# Schematic.net
KiCad netlist of a schematic drawn in Altium Designer
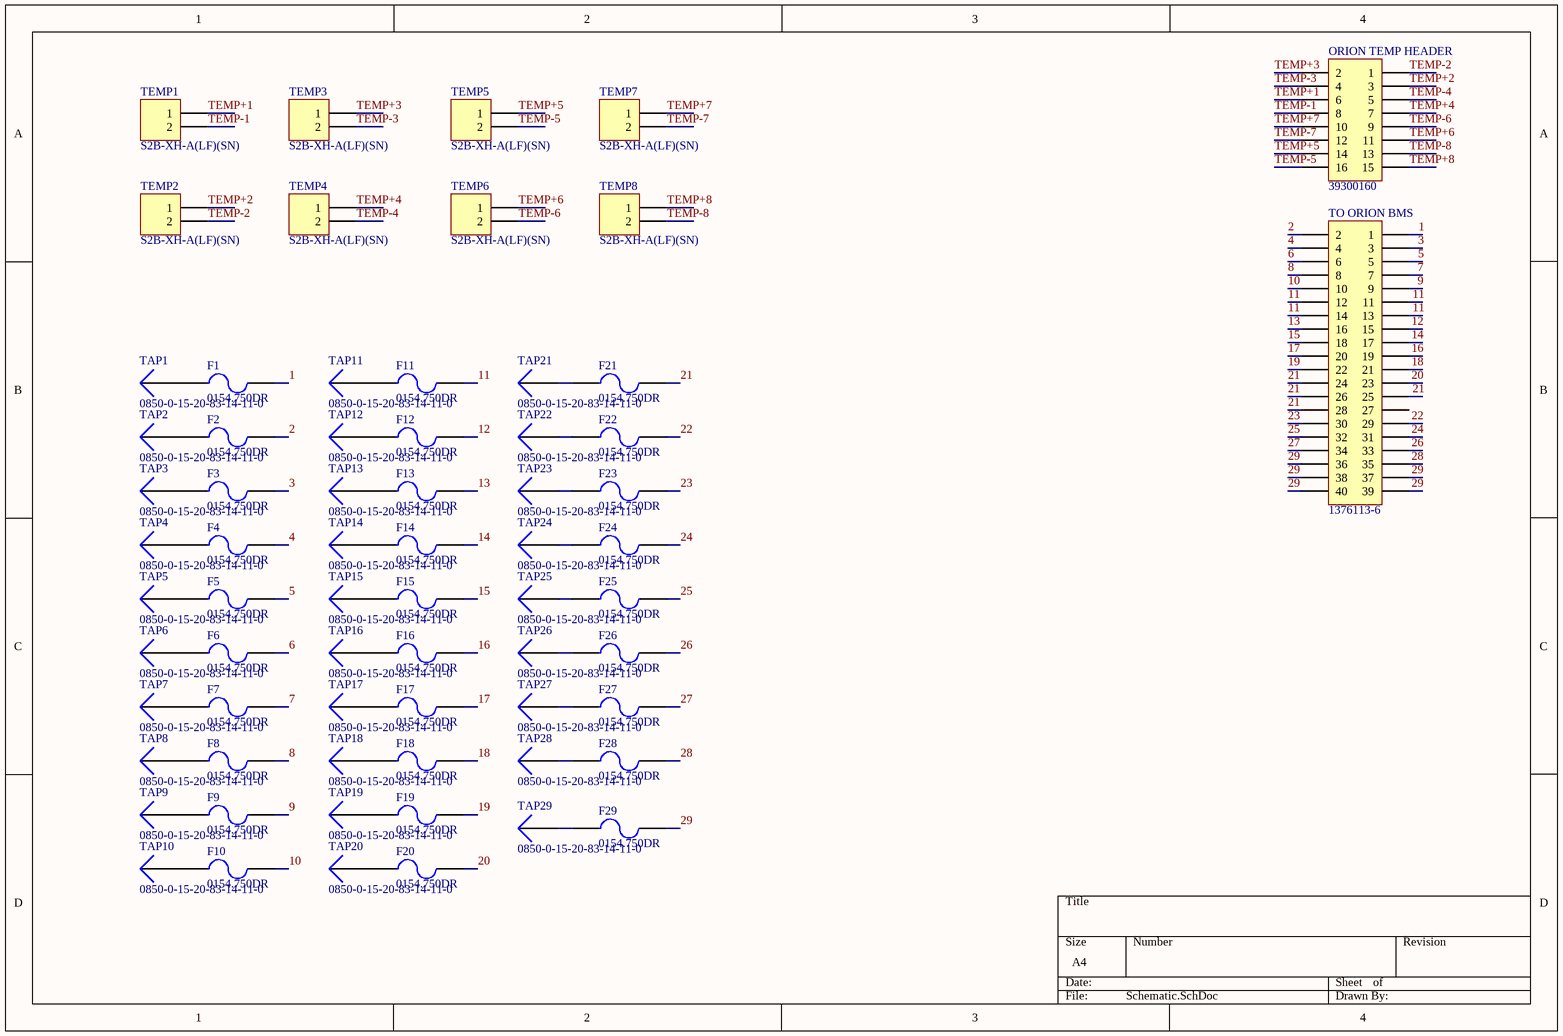
[diagram p0: Schematic.SchDoc]

(export (version "E")
  (design (tool "Eeschema 10.0.6"))
  (components
    (comp (ref "F1")
      (value "0154.750DR")
      (footprint "Omni BLOK 0154")
      (description "FUSE BOARD MNT 750MA 125VAC/VDC")
      (fields
        (field (name "MANUFACTURER") "LittelFuse Inc")
        (field (name "DIGIKEY PART NUMBER") "F1221CT-ND")
      )
      (libsource (lib "ts_20-standard-library") (part "Fuse"))
    )
    (comp (ref "F2")
      (value "0154.750DR")
      (footprint "Omni BLOK 0154")
      (description "FUSE BOARD MNT 750MA 125VAC/VDC")
      (fields
        (field (name "MANUFACTURER") "LittelFuse Inc")
        (field (name "DIGIKEY PART NUMBER") "F1221CT-ND")
      )
      (libsource (lib "ts_20-standard-library") (part "Fuse"))
    )
    (comp (ref "F3")
      (value "0154.750DR")
      (footprint "Omni BLOK 0154")
      (description "FUSE BOARD MNT 750MA 125VAC/VDC")
      (fields
        (field (name "MANUFACTURER") "LittelFuse Inc")
        (field (name "DIGIKEY PART NUMBER") "F1221CT-ND")
      )
      (libsource (lib "ts_20-standard-library") (part "Fuse"))
    )
    (comp (ref "F4")
      (value "0154.750DR")
      (footprint "Omni BLOK 0154")
      (description "FUSE BOARD MNT 750MA 125VAC/VDC")
      (fields
        (field (name "MANUFACTURER") "LittelFuse Inc")
        (field (name "DIGIKEY PART NUMBER") "F1221CT-ND")
      )
      (libsource (lib "ts_20-standard-library") (part "Fuse"))
    )
    (comp (ref "F5")
      (value "0154.750DR")
      (footprint "Omni BLOK 0154")
      (description "FUSE BOARD MNT 750MA 125VAC/VDC")
      (fields
        (field (name "MANUFACTURER") "LittelFuse Inc")
        (field (name "DIGIKEY PART NUMBER") "F1221CT-ND")
      )
      (libsource (lib "ts_20-standard-library") (part "Fuse"))
    )
    (comp (ref "F6")
      (value "0154.750DR")
      (footprint "Omni BLOK 0154")
      (description "FUSE BOARD MNT 750MA 125VAC/VDC")
      (fields
        (field (name "MANUFACTURER") "LittelFuse Inc")
        (field (name "DIGIKEY PART NUMBER") "F1221CT-ND")
      )
      (libsource (lib "ts_20-standard-library") (part "Fuse"))
    )
    (comp (ref "F7")
      (value "0154.750DR")
      (footprint "Omni BLOK 0154")
      (description "FUSE BOARD MNT 750MA 125VAC/VDC")
      (fields
        (field (name "MANUFACTURER") "LittelFuse Inc")
        (field (name "DIGIKEY PART NUMBER") "F1221CT-ND")
      )
      (libsource (lib "ts_20-standard-library") (part "Fuse"))
    )
    (comp (ref "F8")
      (value "0154.750DR")
      (footprint "Omni BLOK 0154")
      (description "FUSE BOARD MNT 750MA 125VAC/VDC")
      (fields
        (field (name "MANUFACTURER") "LittelFuse Inc")
        (field (name "DIGIKEY PART NUMBER") "F1221CT-ND")
      )
      (libsource (lib "ts_20-standard-library") (part "Fuse"))
    )
    (comp (ref "F9")
      (value "0154.750DR")
      (footprint "Omni BLOK 0154")
      (description "FUSE BOARD MNT 750MA 125VAC/VDC")
      (fields
        (field (name "MANUFACTURER") "LittelFuse Inc")
        (field (name "DIGIKEY PART NUMBER") "F1221CT-ND")
      )
      (libsource (lib "ts_20-standard-library") (part "Fuse"))
    )
    (comp (ref "F10")
      (value "0154.750DR")
      (footprint "Omni BLOK 0154")
      (description "FUSE BOARD MNT 750MA 125VAC/VDC")
      (fields
        (field (name "MANUFACTURER") "LittelFuse Inc")
        (field (name "DIGIKEY PART NUMBER") "F1221CT-ND")
      )
      (libsource (lib "ts_20-standard-library") (part "Fuse"))
    )
    (comp (ref "F11")
      (value "0154.750DR")
      (footprint "Omni BLOK 0154")
      (description "FUSE BOARD MNT 750MA 125VAC/VDC")
      (fields
        (field (name "MANUFACTURER") "LittelFuse Inc")
        (field (name "DIGIKEY PART NUMBER") "F1221CT-ND")
      )
      (libsource (lib "ts_20-standard-library") (part "Fuse"))
    )
    (comp (ref "F12")
      (value "0154.750DR")
      (footprint "Omni BLOK 0154")
      (description "FUSE BOARD MNT 750MA 125VAC/VDC")
      (fields
        (field (name "MANUFACTURER") "LittelFuse Inc")
        (field (name "DIGIKEY PART NUMBER") "F1221CT-ND")
      )
      (libsource (lib "ts_20-standard-library") (part "Fuse"))
    )
    (comp (ref "F13")
      (value "0154.750DR")
      (footprint "Omni BLOK 0154")
      (description "FUSE BOARD MNT 750MA 125VAC/VDC")
      (fields
        (field (name "MANUFACTURER") "LittelFuse Inc")
        (field (name "DIGIKEY PART NUMBER") "F1221CT-ND")
      )
      (libsource (lib "ts_20-standard-library") (part "Fuse"))
    )
    (comp (ref "F14")
      (value "0154.750DR")
      (footprint "Omni BLOK 0154")
      (description "FUSE BOARD MNT 750MA 125VAC/VDC")
      (fields
        (field (name "MANUFACTURER") "LittelFuse Inc")
        (field (name "DIGIKEY PART NUMBER") "F1221CT-ND")
      )
      (libsource (lib "ts_20-standard-library") (part "Fuse"))
    )
    (comp (ref "F15")
      (value "0154.750DR")
      (footprint "Omni BLOK 0154")
      (description "FUSE BOARD MNT 750MA 125VAC/VDC")
      (fields
        (field (name "MANUFACTURER") "LittelFuse Inc")
        (field (name "DIGIKEY PART NUMBER") "F1221CT-ND")
      )
      (libsource (lib "ts_20-standard-library") (part "Fuse"))
    )
    (comp (ref "F16")
      (value "0154.750DR")
      (footprint "Omni BLOK 0154")
      (description "FUSE BOARD MNT 750MA 125VAC/VDC")
      (fields
        (field (name "MANUFACTURER") "LittelFuse Inc")
        (field (name "DIGIKEY PART NUMBER") "F1221CT-ND")
      )
      (libsource (lib "ts_20-standard-library") (part "Fuse"))
    )
    (comp (ref "F17")
      (value "0154.750DR")
      (footprint "Omni BLOK 0154")
      (description "FUSE BOARD MNT 750MA 125VAC/VDC")
      (fields
        (field (name "MANUFACTURER") "LittelFuse Inc")
        (field (name "DIGIKEY PART NUMBER") "F1221CT-ND")
      )
      (libsource (lib "ts_20-standard-library") (part "Fuse"))
    )
    (comp (ref "F18")
      (value "0154.750DR")
      (footprint "Omni BLOK 0154")
      (description "FUSE BOARD MNT 750MA 125VAC/VDC")
      (fields
        (field (name "MANUFACTURER") "LittelFuse Inc")
        (field (name "DIGIKEY PART NUMBER") "F1221CT-ND")
      )
      (libsource (lib "ts_20-standard-library") (part "Fuse"))
    )
    (comp (ref "F19")
      (value "0154.750DR")
      (footprint "Omni BLOK 0154")
      (description "FUSE BOARD MNT 750MA 125VAC/VDC")
      (fields
        (field (name "MANUFACTURER") "LittelFuse Inc")
        (field (name "DIGIKEY PART NUMBER") "F1221CT-ND")
      )
      (libsource (lib "ts_20-standard-library") (part "Fuse"))
    )
    (comp (ref "F20")
      (value "0154.750DR")
      (footprint "Omni BLOK 0154")
      (description "FUSE BOARD MNT 750MA 125VAC/VDC")
      (fields
        (field (name "MANUFACTURER") "LittelFuse Inc")
        (field (name "DIGIKEY PART NUMBER") "F1221CT-ND")
      )
      (libsource (lib "ts_20-standard-library") (part "Fuse"))
    )
    (comp (ref "F21")
      (value "0154.750DR")
      (footprint "Omni BLOK 0154")
      (description "FUSE BOARD MNT 750MA 125VAC/VDC")
      (fields
        (field (name "MANUFACTURER") "LittelFuse Inc")
        (field (name "DIGIKEY PART NUMBER") "F1221CT-ND")
      )
      (libsource (lib "ts_20-standard-library") (part "Fuse"))
    )
    (comp (ref "F22")
      (value "0154.750DR")
      (footprint "Omni BLOK 0154")
      (description "FUSE BOARD MNT 750MA 125VAC/VDC")
      (fields
        (field (name "MANUFACTURER") "LittelFuse Inc")
        (field (name "DIGIKEY PART NUMBER") "F1221CT-ND")
      )
      (libsource (lib "ts_20-standard-library") (part "Fuse"))
    )
    (comp (ref "F23")
      (value "0154.750DR")
      (footprint "Omni BLOK 0154")
      (description "FUSE BOARD MNT 750MA 125VAC/VDC")
      (fields
        (field (name "MANUFACTURER") "LittelFuse Inc")
        (field (name "DIGIKEY PART NUMBER") "F1221CT-ND")
      )
      (libsource (lib "ts_20-standard-library") (part "Fuse"))
    )
    (comp (ref "F24")
      (value "0154.750DR")
      (footprint "Omni BLOK 0154")
      (description "FUSE BOARD MNT 750MA 125VAC/VDC")
      (fields
        (field (name "MANUFACTURER") "LittelFuse Inc")
        (field (name "DIGIKEY PART NUMBER") "F1221CT-ND")
      )
      (libsource (lib "ts_20-standard-library") (part "Fuse"))
    )
    (comp (ref "F25")
      (value "0154.750DR")
      (footprint "Omni BLOK 0154")
      (description "FUSE BOARD MNT 750MA 125VAC/VDC")
      (fields
        (field (name "MANUFACTURER") "LittelFuse Inc")
        (field (name "DIGIKEY PART NUMBER") "F1221CT-ND")
      )
      (libsource (lib "ts_20-standard-library") (part "Fuse"))
    )
    (comp (ref "F26")
      (value "0154.750DR")
      (footprint "Omni BLOK 0154")
      (description "FUSE BOARD MNT 750MA 125VAC/VDC")
      (fields
        (field (name "MANUFACTURER") "LittelFuse Inc")
        (field (name "DIGIKEY PART NUMBER") "F1221CT-ND")
      )
      (libsource (lib "ts_20-standard-library") (part "Fuse"))
    )
    (comp (ref "F27")
      (value "0154.750DR")
      (footprint "Omni BLOK 0154")
      (description "FUSE BOARD MNT 750MA 125VAC/VDC")
      (fields
        (field (name "MANUFACTURER") "LittelFuse Inc")
        (field (name "DIGIKEY PART NUMBER") "F1221CT-ND")
      )
      (libsource (lib "ts_20-standard-library") (part "Fuse"))
    )
    (comp (ref "F28")
      (value "0154.750DR")
      (footprint "Omni BLOK 0154")
      (description "FUSE BOARD MNT 750MA 125VAC/VDC")
      (fields
        (field (name "MANUFACTURER") "LittelFuse Inc")
        (field (name "DIGIKEY PART NUMBER") "F1221CT-ND")
      )
      (libsource (lib "ts_20-standard-library") (part "Fuse"))
    )
    (comp (ref "F29")
      (value "0154.750DR")
      (footprint "Omni BLOK 0154")
      (description "FUSE BOARD MNT 750MA 125VAC/VDC")
      (fields
        (field (name "MANUFACTURER") "LittelFuse Inc")
        (field (name "DIGIKEY PART NUMBER") "F1221CT-ND")
      )
      (libsource (lib "ts_20-standard-library") (part "Fuse"))
    )
    (comp (ref "ORION TEMP HEADER")
      (value "39300160")
      (footprint "39300160")
      (fields (field (name "DIGIKEY PART NUMBER") "WM21358-ND") (field (name "CONTACT") "Tin"))
      (libsource (lib "ts_20-standard-connectors") (part "39300160"))
    )
    (comp (ref "TAP1")
      (value "0850-0-15-20-83-14-11-0")
      (footprint "0850-0-15-20-83-14-11-0")
      (fields (field (name "DIGIKEY PART NUMBER") "ED90436-ND") (field (name "CONTACT") "Gold"))
      (libsource (lib "ts_20-standard-connectors") (part "0850-0-15-20-83-14-11-0"))
    )
    (comp (ref "TAP2")
      (value "0850-0-15-20-83-14-11-0")
      (footprint "0850-0-15-20-83-14-11-0")
      (fields (field (name "DIGIKEY PART NUMBER") "ED90436-ND") (field (name "CONTACT") "Gold"))
      (libsource (lib "ts_20-standard-connectors") (part "0850-0-15-20-83-14-11-0"))
    )
    (comp (ref "TAP3")
      (value "0850-0-15-20-83-14-11-0")
      (footprint "0850-0-15-20-83-14-11-0")
      (fields (field (name "DIGIKEY PART NUMBER") "ED90436-ND") (field (name "CONTACT") "Gold"))
      (libsource (lib "ts_20-standard-connectors") (part "0850-0-15-20-83-14-11-0"))
    )
    (comp (ref "TAP4")
      (value "0850-0-15-20-83-14-11-0")
      (footprint "0850-0-15-20-83-14-11-0")
      (fields (field (name "DIGIKEY PART NUMBER") "ED90436-ND") (field (name "CONTACT") "Gold"))
      (libsource (lib "ts_20-standard-connectors") (part "0850-0-15-20-83-14-11-0"))
    )
    (comp (ref "TAP5")
      (value "0850-0-15-20-83-14-11-0")
      (footprint "0850-0-15-20-83-14-11-0")
      (fields (field (name "DIGIKEY PART NUMBER") "ED90436-ND") (field (name "CONTACT") "Gold"))
      (libsource (lib "ts_20-standard-connectors") (part "0850-0-15-20-83-14-11-0"))
    )
    (comp (ref "TAP6")
      (value "0850-0-15-20-83-14-11-0")
      (footprint "0850-0-15-20-83-14-11-0")
      (fields (field (name "DIGIKEY PART NUMBER") "ED90436-ND") (field (name "CONTACT") "Gold"))
      (libsource (lib "ts_20-standard-connectors") (part "0850-0-15-20-83-14-11-0"))
    )
    (comp (ref "TAP7")
      (value "0850-0-15-20-83-14-11-0")
      (footprint "0850-0-15-20-83-14-11-0")
      (fields (field (name "DIGIKEY PART NUMBER") "ED90436-ND") (field (name "CONTACT") "Gold"))
      (libsource (lib "ts_20-standard-connectors") (part "0850-0-15-20-83-14-11-0"))
    )
    (comp (ref "TAP8")
      (value "0850-0-15-20-83-14-11-0")
      (footprint "0850-0-15-20-83-14-11-0")
      (fields (field (name "DIGIKEY PART NUMBER") "ED90436-ND") (field (name "CONTACT") "Gold"))
      (libsource (lib "ts_20-standard-connectors") (part "0850-0-15-20-83-14-11-0"))
    )
    (comp (ref "TAP9")
      (value "0850-0-15-20-83-14-11-0")
      (footprint "0850-0-15-20-83-14-11-0")
      (fields (field (name "DIGIKEY PART NUMBER") "ED90436-ND") (field (name "CONTACT") "Gold"))
      (libsource (lib "ts_20-standard-connectors") (part "0850-0-15-20-83-14-11-0"))
    )
    (comp (ref "TAP10")
      (value "0850-0-15-20-83-14-11-0")
      (footprint "0850-0-15-20-83-14-11-0")
      (fields (field (name "DIGIKEY PART NUMBER") "ED90436-ND") (field (name "CONTACT") "Gold"))
      (libsource (lib "ts_20-standard-connectors") (part "0850-0-15-20-83-14-11-0"))
    )
    (comp (ref "TAP11")
      (value "0850-0-15-20-83-14-11-0")
      (footprint "0850-0-15-20-83-14-11-0")
      (fields (field (name "DIGIKEY PART NUMBER") "ED90436-ND") (field (name "CONTACT") "Gold"))
      (libsource (lib "ts_20-standard-connectors") (part "0850-0-15-20-83-14-11-0"))
    )
    (comp (ref "TAP12")
      (value "0850-0-15-20-83-14-11-0")
      (footprint "0850-0-15-20-83-14-11-0")
      (fields (field (name "DIGIKEY PART NUMBER") "ED90436-ND") (field (name "CONTACT") "Gold"))
      (libsource (lib "ts_20-standard-connectors") (part "0850-0-15-20-83-14-11-0"))
    )
    (comp (ref "TAP13")
      (value "0850-0-15-20-83-14-11-0")
      (footprint "0850-0-15-20-83-14-11-0")
      (fields (field (name "DIGIKEY PART NUMBER") "ED90436-ND") (field (name "CONTACT") "Gold"))
      (libsource (lib "ts_20-standard-connectors") (part "0850-0-15-20-83-14-11-0"))
    )
    (comp (ref "TAP14")
      (value "0850-0-15-20-83-14-11-0")
      (footprint "0850-0-15-20-83-14-11-0")
      (fields (field (name "DIGIKEY PART NUMBER") "ED90436-ND") (field (name "CONTACT") "Gold"))
      (libsource (lib "ts_20-standard-connectors") (part "0850-0-15-20-83-14-11-0"))
    )
    (comp (ref "TAP15")
      (value "0850-0-15-20-83-14-11-0")
      (footprint "0850-0-15-20-83-14-11-0")
      (fields (field (name "DIGIKEY PART NUMBER") "ED90436-ND") (field (name "CONTACT") "Gold"))
      (libsource (lib "ts_20-standard-connectors") (part "0850-0-15-20-83-14-11-0"))
    )
    (comp (ref "TAP16")
      (value "0850-0-15-20-83-14-11-0")
      (footprint "0850-0-15-20-83-14-11-0")
      (fields (field (name "DIGIKEY PART NUMBER") "ED90436-ND") (field (name "CONTACT") "Gold"))
      (libsource (lib "ts_20-standard-connectors") (part "0850-0-15-20-83-14-11-0"))
    )
    (comp (ref "TAP17")
      (value "0850-0-15-20-83-14-11-0")
      (footprint "0850-0-15-20-83-14-11-0")
      (fields (field (name "DIGIKEY PART NUMBER") "ED90436-ND") (field (name "CONTACT") "Gold"))
      (libsource (lib "ts_20-standard-connectors") (part "0850-0-15-20-83-14-11-0"))
    )
    (comp (ref "TAP18")
      (value "0850-0-15-20-83-14-11-0")
      (footprint "0850-0-15-20-83-14-11-0")
      (fields (field (name "DIGIKEY PART NUMBER") "ED90436-ND") (field (name "CONTACT") "Gold"))
      (libsource (lib "ts_20-standard-connectors") (part "0850-0-15-20-83-14-11-0"))
    )
    (comp (ref "TAP19")
      (value "0850-0-15-20-83-14-11-0")
      (footprint "0850-0-15-20-83-14-11-0")
      (fields (field (name "DIGIKEY PART NUMBER") "ED90436-ND") (field (name "CONTACT") "Gold"))
      (libsource (lib "ts_20-standard-connectors") (part "0850-0-15-20-83-14-11-0"))
    )
    (comp (ref "TAP20")
      (value "0850-0-15-20-83-14-11-0")
      (footprint "0850-0-15-20-83-14-11-0")
      (fields (field (name "DIGIKEY PART NUMBER") "ED90436-ND") (field (name "CONTACT") "Gold"))
      (libsource (lib "ts_20-standard-connectors") (part "0850-0-15-20-83-14-11-0"))
    )
    (comp (ref "TAP21")
      (value "0850-0-15-20-83-14-11-0")
      (footprint "0850-0-15-20-83-14-11-0")
      (fields (field (name "DIGIKEY PART NUMBER") "ED90436-ND") (field (name "CONTACT") "Gold"))
      (libsource (lib "ts_20-standard-connectors") (part "0850-0-15-20-83-14-11-0"))
    )
    (comp (ref "TAP22")
      (value "0850-0-15-20-83-14-11-0")
      (footprint "0850-0-15-20-83-14-11-0")
      (fields (field (name "DIGIKEY PART NUMBER") "ED90436-ND") (field (name "CONTACT") "Gold"))
      (libsource (lib "ts_20-standard-connectors") (part "0850-0-15-20-83-14-11-0"))
    )
    (comp (ref "TAP23")
      (value "0850-0-15-20-83-14-11-0")
      (footprint "0850-0-15-20-83-14-11-0")
      (fields (field (name "DIGIKEY PART NUMBER") "ED90436-ND") (field (name "CONTACT") "Gold"))
      (libsource (lib "ts_20-standard-connectors") (part "0850-0-15-20-83-14-11-0"))
    )
    (comp (ref "TAP24")
      (value "0850-0-15-20-83-14-11-0")
      (footprint "0850-0-15-20-83-14-11-0")
      (fields (field (name "DIGIKEY PART NUMBER") "ED90436-ND") (field (name "CONTACT") "Gold"))
      (libsource (lib "ts_20-standard-connectors") (part "0850-0-15-20-83-14-11-0"))
    )
    (comp (ref "TAP25")
      (value "0850-0-15-20-83-14-11-0")
      (footprint "0850-0-15-20-83-14-11-0")
      (fields (field (name "DIGIKEY PART NUMBER") "ED90436-ND") (field (name "CONTACT") "Gold"))
      (libsource (lib "ts_20-standard-connectors") (part "0850-0-15-20-83-14-11-0"))
    )
    (comp (ref "TAP26")
      (value "0850-0-15-20-83-14-11-0")
      (footprint "0850-0-15-20-83-14-11-0")
      (fields (field (name "DIGIKEY PART NUMBER") "ED90436-ND") (field (name "CONTACT") "Gold"))
      (libsource (lib "ts_20-standard-connectors") (part "0850-0-15-20-83-14-11-0"))
    )
    (comp (ref "TAP27")
      (value "0850-0-15-20-83-14-11-0")
      (footprint "0850-0-15-20-83-14-11-0")
      (fields (field (name "DIGIKEY PART NUMBER") "ED90436-ND") (field (name "CONTACT") "Gold"))
      (libsource (lib "ts_20-standard-connectors") (part "0850-0-15-20-83-14-11-0"))
    )
    (comp (ref "TAP28")
      (value "0850-0-15-20-83-14-11-0")
      (footprint "0850-0-15-20-83-14-11-0")
      (fields (field (name "DIGIKEY PART NUMBER") "ED90436-ND") (field (name "CONTACT") "Gold"))
      (libsource (lib "ts_20-standard-connectors") (part "0850-0-15-20-83-14-11-0"))
    )
    (comp (ref "TAP29")
      (value "0850-0-15-20-83-14-11-0")
      (footprint "0850-0-15-20-83-14-11-0")
      (fields (field (name "DIGIKEY PART NUMBER") "ED90436-ND") (field (name "CONTACT") "Gold"))
      (libsource (lib "ts_20-standard-connectors") (part "0850-0-15-20-83-14-11-0"))
    )
    (comp (ref "TEMP1") (value "S2B-XH-A(LF)(SN)") (libsource (lib "JST") (part "S2B-XH-A(LF)(SN)")))
    (comp (ref "TEMP2") (value "S2B-XH-A(LF)(SN)") (libsource (lib "JST") (part "S2B-XH-A(LF)(SN)")))
    (comp (ref "TEMP3") (value "S2B-XH-A(LF)(SN)") (libsource (lib "JST") (part "S2B-XH-A(LF)(SN)")))
    (comp (ref "TEMP4") (value "S2B-XH-A(LF)(SN)") (libsource (lib "JST") (part "S2B-XH-A(LF)(SN)")))
    (comp (ref "TEMP5") (value "S2B-XH-A(LF)(SN)") (libsource (lib "JST") (part "S2B-XH-A(LF)(SN)")))
    (comp (ref "TEMP6") (value "S2B-XH-A(LF)(SN)") (libsource (lib "JST") (part "S2B-XH-A(LF)(SN)")))
    (comp (ref "TEMP7") (value "S2B-XH-A(LF)(SN)") (libsource (lib "JST") (part "S2B-XH-A(LF)(SN)")))
    (comp (ref "TEMP8") (value "S2B-XH-A(LF)(SN)") (libsource (lib "JST") (part "S2B-XH-A(LF)(SN)")))
    (comp (ref "TO ORION BMS")
      (value "1376113-6")
      (footprint "1376113-6")
      (fields (field (name "DIGIKEY PART NUMBER") "A122206-ND") (field (name "CONTACT") "gold"))
      (libsource (lib "ts_20-standard-connectors") (part "1376113-6"))
    )
  )
  (nets
    (net (code "1") (name "/1") (class "Default")
      (node (ref "F1") (pin "2") (pinfunction "2_2") (pintype "passive"))
      (node (ref "TO ORION BMS") (pin "1") (pinfunction "1_1") (pintype "passive"))
    )
    (net (code "2") (name "/2") (class "Default")
      (node (ref "F2") (pin "2") (pinfunction "2_2") (pintype "passive"))
      (node (ref "TO ORION BMS") (pin "2") (pinfunction "2_2") (pintype "passive"))
    )
    (net (code "3") (name "/3") (class "Default")
      (node (ref "F3") (pin "2") (pinfunction "2_2") (pintype "passive"))
      (node (ref "TO ORION BMS") (pin "3") (pinfunction "3_3") (pintype "passive"))
    )
    (net (code "4") (name "/4") (class "Default")
      (node (ref "F4") (pin "2") (pinfunction "2_2") (pintype "passive"))
      (node (ref "TO ORION BMS") (pin "4") (pinfunction "4_4") (pintype "passive"))
    )
    (net (code "5") (name "/5") (class "Default")
      (node (ref "F5") (pin "2") (pinfunction "2_2") (pintype "passive"))
      (node (ref "TO ORION BMS") (pin "5") (pinfunction "5_5") (pintype "passive"))
    )
    (net (code "6") (name "/6") (class "Default")
      (node (ref "F6") (pin "2") (pinfunction "2_2") (pintype "passive"))
      (node (ref "TO ORION BMS") (pin "6") (pinfunction "6_6") (pintype "passive"))
    )
    (net (code "7") (name "/7") (class "Default")
      (node (ref "F7") (pin "2") (pinfunction "2_2") (pintype "passive"))
      (node (ref "TO ORION BMS") (pin "7") (pinfunction "7_7") (pintype "passive"))
    )
    (net (code "8") (name "/8") (class "Default")
      (node (ref "F8") (pin "2") (pinfunction "2_2") (pintype "passive"))
      (node (ref "TO ORION BMS") (pin "8") (pinfunction "8_8") (pintype "passive"))
    )
    (net (code "9") (name "/9") (class "Default")
      (node (ref "F9") (pin "2") (pinfunction "2_2") (pintype "passive"))
      (node (ref "TO ORION BMS") (pin "9") (pinfunction "9_9") (pintype "passive"))
    )
    (net (code "10") (name "/10") (class "Default")
      (node (ref "F10") (pin "2") (pinfunction "2_2") (pintype "passive"))
      (node (ref "TO ORION BMS") (pin "10") (pinfunction "10_10") (pintype "passive"))
    )
    (net (code "11") (name "/11") (class "Default")
      (node (ref "F11") (pin "2") (pinfunction "2_2") (pintype "passive"))
      (node (ref "TO ORION BMS") (pin "11") (pinfunction "11_11") (pintype "passive"))
      (node (ref "TO ORION BMS") (pin "12") (pinfunction "12_12") (pintype "passive"))
      (node (ref "TO ORION BMS") (pin "13") (pinfunction "13_13") (pintype "passive"))
      (node (ref "TO ORION BMS") (pin "14") (pinfunction "14_14") (pintype "passive"))
    )
    (net (code "12") (name "/12") (class "Default")
      (node (ref "F12") (pin "2") (pinfunction "2_2") (pintype "passive"))
      (node (ref "TO ORION BMS") (pin "15") (pinfunction "15_15") (pintype "passive"))
    )
    (net (code "13") (name "/13") (class "Default")
      (node (ref "F13") (pin "2") (pinfunction "2_2") (pintype "passive"))
      (node (ref "TO ORION BMS") (pin "16") (pinfunction "16_16") (pintype "passive"))
    )
    (net (code "14") (name "/14") (class "Default")
      (node (ref "F14") (pin "2") (pinfunction "2_2") (pintype "passive"))
      (node (ref "TO ORION BMS") (pin "17") (pinfunction "17_17") (pintype "passive"))
    )
    (net (code "15") (name "/15") (class "Default")
      (node (ref "F15") (pin "2") (pinfunction "2_2") (pintype "passive"))
      (node (ref "TO ORION BMS") (pin "18") (pinfunction "18_18") (pintype "passive"))
    )
    (net (code "16") (name "/16") (class "Default")
      (node (ref "F16") (pin "2") (pinfunction "2_2") (pintype "passive"))
      (node (ref "TO ORION BMS") (pin "19") (pinfunction "19_19") (pintype "passive"))
    )
    (net (code "17") (name "/17") (class "Default")
      (node (ref "F17") (pin "2") (pinfunction "2_2") (pintype "passive"))
      (node (ref "TO ORION BMS") (pin "20") (pinfunction "20_20") (pintype "passive"))
    )
    (net (code "18") (name "/18") (class "Default")
      (node (ref "F18") (pin "2") (pinfunction "2_2") (pintype "passive"))
      (node (ref "TO ORION BMS") (pin "21") (pinfunction "21_21") (pintype "passive"))
    )
    (net (code "19") (name "/19") (class "Default")
      (node (ref "F19") (pin "2") (pinfunction "2_2") (pintype "passive"))
      (node (ref "TO ORION BMS") (pin "22") (pinfunction "22_22") (pintype "passive"))
    )
    (net (code "20") (name "/20") (class "Default")
      (node (ref "F20") (pin "2") (pinfunction "2_2") (pintype "passive"))
      (node (ref "TO ORION BMS") (pin "23") (pinfunction "23_23") (pintype "passive"))
    )
    (net (code "21") (name "/21") (class "Default")
      (node (ref "F21") (pin "2") (pinfunction "2_2") (pintype "passive"))
      (node (ref "TO ORION BMS") (pin "24") (pinfunction "24_24") (pintype "passive"))
      (node (ref "TO ORION BMS") (pin "25") (pinfunction "25_25") (pintype "passive"))
      (node (ref "TO ORION BMS") (pin "26") (pinfunction "26_26") (pintype "passive"))
      (node (ref "TO ORION BMS") (pin "28") (pinfunction "28_28") (pintype "passive"))
    )
    (net (code "22") (name "/22") (class "Default")
      (node (ref "F22") (pin "2") (pinfunction "2_2") (pintype "passive"))
      (node (ref "TO ORION BMS") (pin "29") (pinfunction "29_29") (pintype "passive"))
    )
    (net (code "23") (name "/23") (class "Default")
      (node (ref "F23") (pin "2") (pinfunction "2_2") (pintype "passive"))
      (node (ref "TO ORION BMS") (pin "30") (pinfunction "30_30") (pintype "passive"))
    )
    (net (code "24") (name "/24") (class "Default")
      (node (ref "F24") (pin "2") (pinfunction "2_2") (pintype "passive"))
      (node (ref "TO ORION BMS") (pin "31") (pinfunction "31_31") (pintype "passive"))
    )
    (net (code "25") (name "/25") (class "Default")
      (node (ref "F25") (pin "2") (pinfunction "2_2") (pintype "passive"))
      (node (ref "TO ORION BMS") (pin "32") (pinfunction "32_32") (pintype "passive"))
    )
    (net (code "26") (name "/26") (class "Default")
      (node (ref "F26") (pin "2") (pinfunction "2_2") (pintype "passive"))
      (node (ref "TO ORION BMS") (pin "33") (pinfunction "33_33") (pintype "passive"))
    )
    (net (code "27") (name "/27") (class "Default")
      (node (ref "F27") (pin "2") (pinfunction "2_2") (pintype "passive"))
      (node (ref "TO ORION BMS") (pin "34") (pinfunction "34_34") (pintype "passive"))
    )
    (net (code "28") (name "/28") (class "Default")
      (node (ref "F28") (pin "2") (pinfunction "2_2") (pintype "passive"))
      (node (ref "TO ORION BMS") (pin "35") (pinfunction "35_35") (pintype "passive"))
    )
    (net (code "29") (name "/29") (class "Default")
      (node (ref "F29") (pin "2") (pinfunction "2_2") (pintype "passive"))
      (node (ref "TO ORION BMS") (pin "36") (pinfunction "36_36") (pintype "passive"))
      (node (ref "TO ORION BMS") (pin "37") (pinfunction "37_37") (pintype "passive"))
      (node (ref "TO ORION BMS") (pin "38") (pinfunction "38_38") (pintype "passive"))
      (node (ref "TO ORION BMS") (pin "39") (pinfunction "39_39") (pintype "passive"))
      (node (ref "TO ORION BMS") (pin "40") (pinfunction "40_40") (pintype "passive"))
    )
    (net (code "30") (name "/TEMP+1") (class "Default")
      (node (ref "ORION TEMP HEADER") (pin "6") (pinfunction "6_6") (pintype "passive"))
      (node (ref "TEMP1") (pin "1") (pinfunction "1_1") (pintype "passive"))
    )
    (net (code "31") (name "/TEMP+2") (class "Default")
      (node (ref "ORION TEMP HEADER") (pin "3") (pinfunction "3_3") (pintype "passive"))
      (node (ref "TEMP2") (pin "1") (pinfunction "1_1") (pintype "passive"))
    )
    (net (code "32") (name "/TEMP+3") (class "Default")
      (node (ref "ORION TEMP HEADER") (pin "2") (pinfunction "2_2") (pintype "passive"))
      (node (ref "TEMP3") (pin "1") (pinfunction "1_1") (pintype "passive"))
    )
    (net (code "33") (name "/TEMP+4") (class "Default")
      (node (ref "ORION TEMP HEADER") (pin "7") (pinfunction "7_7") (pintype "passive"))
      (node (ref "TEMP4") (pin "1") (pinfunction "1_1") (pintype "passive"))
    )
    (net (code "34") (name "/TEMP+5") (class "Default")
      (node (ref "ORION TEMP HEADER") (pin "14") (pinfunction "14_14") (pintype "passive"))
      (node (ref "TEMP5") (pin "1") (pinfunction "1_1") (pintype "passive"))
    )
    (net (code "35") (name "/TEMP+6") (class "Default")
      (node (ref "ORION TEMP HEADER") (pin "11") (pinfunction "11_11") (pintype "passive"))
      (node (ref "TEMP6") (pin "1") (pinfunction "1_1") (pintype "passive"))
    )
    (net (code "36") (name "/TEMP+7") (class "Default")
      (node (ref "ORION TEMP HEADER") (pin "10") (pinfunction "10_10") (pintype "passive"))
      (node (ref "TEMP7") (pin "1") (pinfunction "1_1") (pintype "passive"))
    )
    (net (code "37") (name "/TEMP+8") (class "Default")
      (node (ref "ORION TEMP HEADER") (pin "15") (pinfunction "15_15") (pintype "passive"))
      (node (ref "TEMP8") (pin "1") (pinfunction "1_1") (pintype "passive"))
    )
    (net (code "38") (name "/TEMP-1") (class "Default")
      (node (ref "ORION TEMP HEADER") (pin "8") (pinfunction "8_8") (pintype "passive"))
      (node (ref "TEMP1") (pin "2") (pinfunction "2_2") (pintype "passive"))
    )
    (net (code "39") (name "/TEMP-2") (class "Default")
      (node (ref "ORION TEMP HEADER") (pin "1") (pinfunction "1_1") (pintype "passive"))
      (node (ref "TEMP2") (pin "2") (pinfunction "2_2") (pintype "passive"))
    )
    (net (code "40") (name "/TEMP-3") (class "Default")
      (node (ref "ORION TEMP HEADER") (pin "4") (pinfunction "4_4") (pintype "passive"))
      (node (ref "TEMP3") (pin "2") (pinfunction "2_2") (pintype "passive"))
    )
    (net (code "41") (name "/TEMP-4") (class "Default")
      (node (ref "ORION TEMP HEADER") (pin "5") (pinfunction "5_5") (pintype "passive"))
      (node (ref "TEMP4") (pin "2") (pinfunction "2_2") (pintype "passive"))
    )
    (net (code "42") (name "/TEMP-5") (class "Default")
      (node (ref "ORION TEMP HEADER") (pin "16") (pinfunction "16_16") (pintype "passive"))
      (node (ref "TEMP5") (pin "2") (pinfunction "2_2") (pintype "passive"))
    )
    (net (code "43") (name "/TEMP-6") (class "Default")
      (node (ref "ORION TEMP HEADER") (pin "9") (pinfunction "9_9") (pintype "passive"))
      (node (ref "TEMP6") (pin "2") (pinfunction "2_2") (pintype "passive"))
    )
    (net (code "44") (name "/TEMP-7") (class "Default")
      (node (ref "ORION TEMP HEADER") (pin "12") (pinfunction "12_12") (pintype "passive"))
      (node (ref "TEMP7") (pin "2") (pinfunction "2_2") (pintype "passive"))
    )
    (net (code "45") (name "/TEMP-8") (class "Default")
      (node (ref "ORION TEMP HEADER") (pin "13") (pinfunction "13_13") (pintype "passive"))
      (node (ref "TEMP8") (pin "2") (pinfunction "2_2") (pintype "passive"))
    )
    (net (code "46") (name "Net-(TAP1-=\"part_number\")") (class "Default")
      (node (ref "F1") (pin "1") (pinfunction "1_1") (pintype "passive"))
      (node (ref "TAP1") (pin "1") (pinfunction "=\"part_number\"_1") (pintype "passive"))
    )
    (net (code "47") (name "Net-(TAP2-=\"part_number\")") (class "Default")
      (node (ref "F2") (pin "1") (pinfunction "1_1") (pintype "passive"))
      (node (ref "TAP2") (pin "1") (pinfunction "=\"part_number\"_1") (pintype "passive"))
    )
    (net (code "48") (name "Net-(TAP3-=\"part_number\")") (class "Default")
      (node (ref "F3") (pin "1") (pinfunction "1_1") (pintype "passive"))
      (node (ref "TAP3") (pin "1") (pinfunction "=\"part_number\"_1") (pintype "passive"))
    )
    (net (code "49") (name "Net-(TAP4-=\"part_number\")") (class "Default")
      (node (ref "F4") (pin "1") (pinfunction "1_1") (pintype "passive"))
      (node (ref "TAP4") (pin "1") (pinfunction "=\"part_number\"_1") (pintype "passive"))
    )
    (net (code "50") (name "Net-(TAP5-=\"part_number\")") (class "Default")
      (node (ref "F5") (pin "1") (pinfunction "1_1") (pintype "passive"))
      (node (ref "TAP5") (pin "1") (pinfunction "=\"part_number\"_1") (pintype "passive"))
    )
    (net (code "51") (name "Net-(TAP6-=\"part_number\")") (class "Default")
      (node (ref "F6") (pin "1") (pinfunction "1_1") (pintype "passive"))
      (node (ref "TAP6") (pin "1") (pinfunction "=\"part_number\"_1") (pintype "passive"))
    )
    (net (code "52") (name "Net-(TAP7-=\"part_number\")") (class "Default")
      (node (ref "F7") (pin "1") (pinfunction "1_1") (pintype "passive"))
      (node (ref "TAP7") (pin "1") (pinfunction "=\"part_number\"_1") (pintype "passive"))
    )
    (net (code "53") (name "Net-(TAP8-=\"part_number\")") (class "Default")
      (node (ref "F8") (pin "1") (pinfunction "1_1") (pintype "passive"))
      (node (ref "TAP8") (pin "1") (pinfunction "=\"part_number\"_1") (pintype "passive"))
    )
    (net (code "54") (name "Net-(TAP9-=\"part_number\")") (class "Default")
      (node (ref "F9") (pin "1") (pinfunction "1_1") (pintype "passive"))
      (node (ref "TAP9") (pin "1") (pinfunction "=\"part_number\"_1") (pintype "passive"))
    )
    (net (code "55") (name "Net-(TAP10-=\"part_number\")") (class "Default")
      (node (ref "F10") (pin "1") (pinfunction "1_1") (pintype "passive"))
      (node (ref "TAP10") (pin "1") (pinfunction "=\"part_number\"_1") (pintype "passive"))
    )
    (net (code "56") (name "Net-(TAP11-=\"part_number\")") (class "Default")
      (node (ref "F11") (pin "1") (pinfunction "1_1") (pintype "passive"))
      (node (ref "TAP11") (pin "1") (pinfunction "=\"part_number\"_1") (pintype "passive"))
    )
    (net (code "57") (name "Net-(TAP12-=\"part_number\")") (class "Default")
      (node (ref "F12") (pin "1") (pinfunction "1_1") (pintype "passive"))
      (node (ref "TAP12") (pin "1") (pinfunction "=\"part_number\"_1") (pintype "passive"))
    )
    (net (code "58") (name "Net-(TAP13-=\"part_number\")") (class "Default")
      (node (ref "F13") (pin "1") (pinfunction "1_1") (pintype "passive"))
      (node (ref "TAP13") (pin "1") (pinfunction "=\"part_number\"_1") (pintype "passive"))
    )
    (net (code "59") (name "Net-(TAP14-=\"part_number\")") (class "Default")
      (node (ref "F14") (pin "1") (pinfunction "1_1") (pintype "passive"))
      (node (ref "TAP14") (pin "1") (pinfunction "=\"part_number\"_1") (pintype "passive"))
    )
    (net (code "60") (name "Net-(TAP15-=\"part_number\")") (class "Default")
      (node (ref "F15") (pin "1") (pinfunction "1_1") (pintype "passive"))
      (node (ref "TAP15") (pin "1") (pinfunction "=\"part_number\"_1") (pintype "passive"))
    )
    (net (code "61") (name "Net-(TAP16-=\"part_number\")") (class "Default")
      (node (ref "F16") (pin "1") (pinfunction "1_1") (pintype "passive"))
      (node (ref "TAP16") (pin "1") (pinfunction "=\"part_number\"_1") (pintype "passive"))
    )
    (net (code "62") (name "Net-(TAP17-=\"part_number\")") (class "Default")
      (node (ref "F17") (pin "1") (pinfunction "1_1") (pintype "passive"))
      (node (ref "TAP17") (pin "1") (pinfunction "=\"part_number\"_1") (pintype "passive"))
    )
    (net (code "63") (name "Net-(TAP18-=\"part_number\")") (class "Default")
      (node (ref "F18") (pin "1") (pinfunction "1_1") (pintype "passive"))
      (node (ref "TAP18") (pin "1") (pinfunction "=\"part_number\"_1") (pintype "passive"))
    )
    (net (code "64") (name "Net-(TAP19-=\"part_number\")") (class "Default")
      (node (ref "F19") (pin "1") (pinfunction "1_1") (pintype "passive"))
      (node (ref "TAP19") (pin "1") (pinfunction "=\"part_number\"_1") (pintype "passive"))
    )
    (net (code "65") (name "Net-(TAP20-=\"part_number\")") (class "Default")
      (node (ref "F20") (pin "1") (pinfunction "1_1") (pintype "passive"))
      (node (ref "TAP20") (pin "1") (pinfunction "=\"part_number\"_1") (pintype "passive"))
    )
    (net (code "66") (name "Net-(TAP21-=\"part_number\")") (class "Default")
      (node (ref "F21") (pin "1") (pinfunction "1_1") (pintype "passive"))
      (node (ref "TAP21") (pin "1") (pinfunction "=\"part_number\"_1") (pintype "passive"))
    )
    (net (code "67") (name "Net-(TAP22-=\"part_number\")") (class "Default")
      (node (ref "F22") (pin "1") (pinfunction "1_1") (pintype "passive"))
      (node (ref "TAP22") (pin "1") (pinfunction "=\"part_number\"_1") (pintype "passive"))
    )
    (net (code "68") (name "Net-(TAP23-=\"part_number\")") (class "Default")
      (node (ref "F23") (pin "1") (pinfunction "1_1") (pintype "passive"))
      (node (ref "TAP23") (pin "1") (pinfunction "=\"part_number\"_1") (pintype "passive"))
    )
    (net (code "69") (name "Net-(TAP24-=\"part_number\")") (class "Default")
      (node (ref "F24") (pin "1") (pinfunction "1_1") (pintype "passive"))
      (node (ref "TAP24") (pin "1") (pinfunction "=\"part_number\"_1") (pintype "passive"))
    )
    (net (code "70") (name "Net-(TAP25-=\"part_number\")") (class "Default")
      (node (ref "F25") (pin "1") (pinfunction "1_1") (pintype "passive"))
      (node (ref "TAP25") (pin "1") (pinfunction "=\"part_number\"_1") (pintype "passive"))
    )
    (net (code "71") (name "Net-(TAP26-=\"part_number\")") (class "Default")
      (node (ref "F26") (pin "1") (pinfunction "1_1") (pintype "passive"))
      (node (ref "TAP26") (pin "1") (pinfunction "=\"part_number\"_1") (pintype "passive"))
    )
    (net (code "72") (name "Net-(TAP27-=\"part_number\")") (class "Default")
      (node (ref "F27") (pin "1") (pinfunction "1_1") (pintype "passive"))
      (node (ref "TAP27") (pin "1") (pinfunction "=\"part_number\"_1") (pintype "passive"))
    )
    (net (code "73") (name "Net-(TAP28-=\"part_number\")") (class "Default")
      (node (ref "F28") (pin "1") (pinfunction "1_1") (pintype "passive"))
      (node (ref "TAP28") (pin "1") (pinfunction "=\"part_number\"_1") (pintype "passive"))
    )
    (net (code "74") (name "Net-(TAP29-=\"part_number\")") (class "Default")
      (node (ref "F29") (pin "1") (pinfunction "1_1") (pintype "passive"))
      (node (ref "TAP29") (pin "1") (pinfunction "=\"part_number\"_1") (pintype "passive"))
    )
    (net (code "75") (name "unconnected-(TO ORION BMS-Pad27)") (class "Default")
      (node (ref "TO ORION BMS") (pin "27") (pinfunction "27_27") (pintype "passive"))
    )
  )
)
